# MINI_SYSTEM_RCT6.net
KiCad netlist of a schematic drawn in Altium Designer
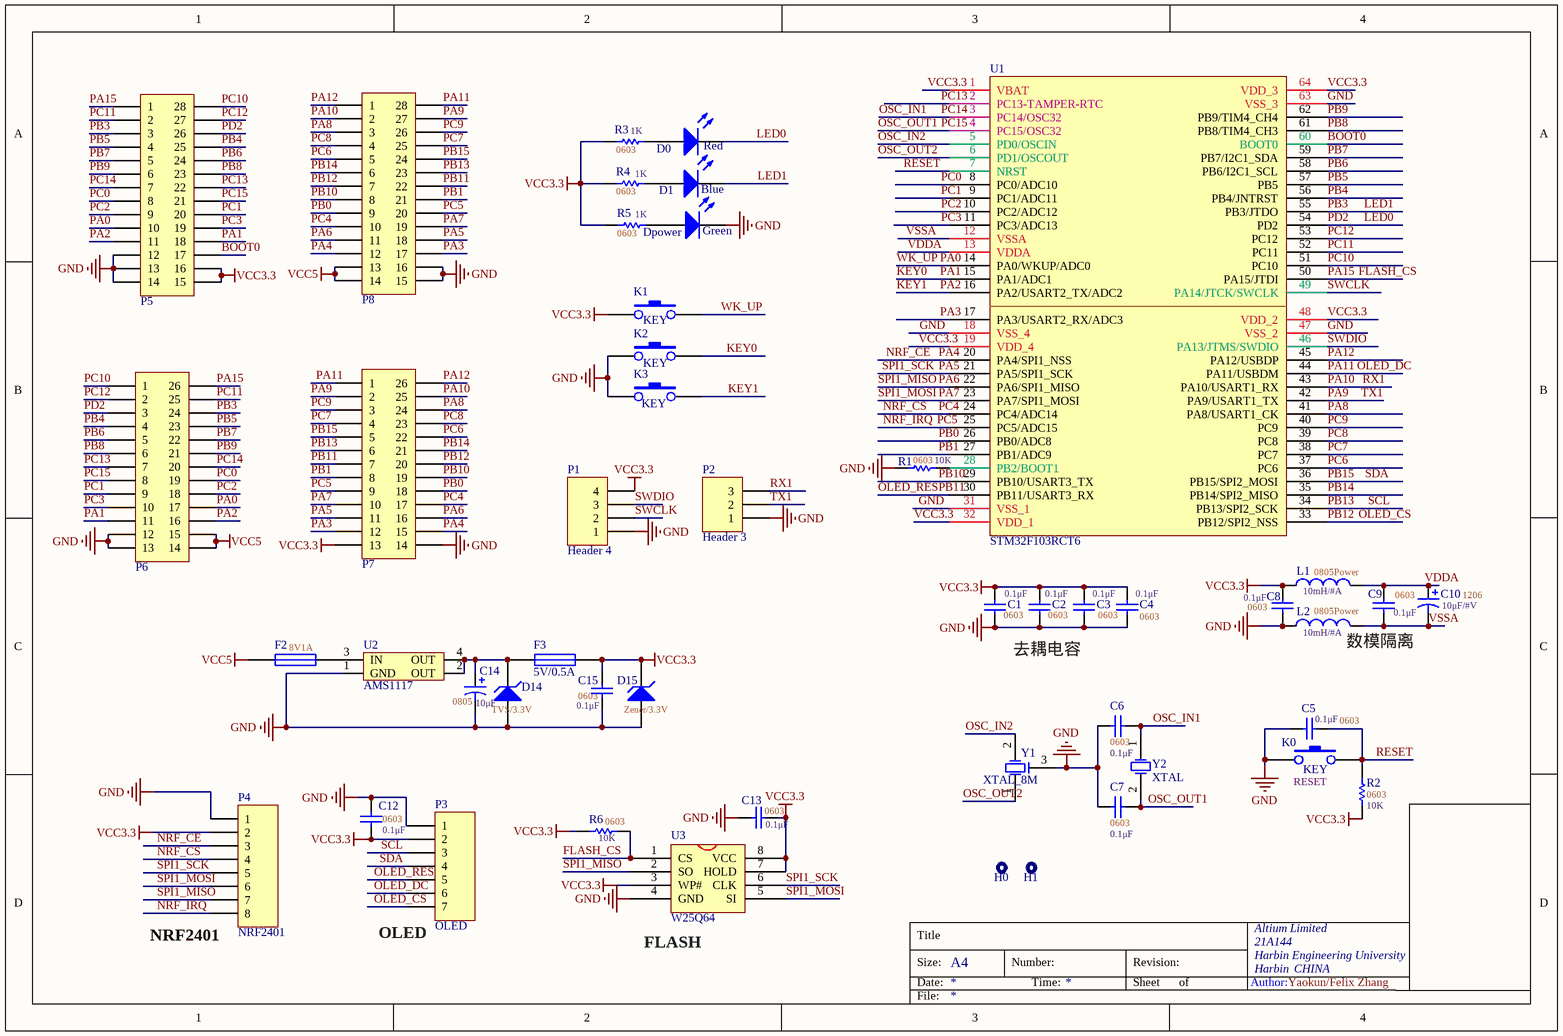
[diagram p0: MINI_SYSTEM_RCT6.SchDoc]

(export (version "E")
  (design (tool "Eeschema 10.0.6"))
  (components
    (comp (ref "C1")
      (value "0.1μF")
      (footprint "CAP_0603_16*08")
      (description "Capacitor")
      (fields
        (field (name "PACKAGEREFERENCE") "0603")
        (field (name "Comment") "0603")
        (field (name "PUBLISHER") "Altium Limited")
      )
      (libsource (lib "Belong_to_Kongkong") (part "Cap"))
    )
    (comp (ref "C2")
      (value "0.1μF")
      (footprint "CAP_0603_16*08")
      (description "Capacitor")
      (fields
        (field (name "PACKAGEREFERENCE") "0603")
        (field (name "Comment") "0603")
        (field (name "PUBLISHER") "Altium Limited")
      )
      (libsource (lib "Belong_to_Kongkong") (part "Cap"))
    )
    (comp (ref "C3")
      (value "0.1μF")
      (footprint "CAP_0603_16*08")
      (description "Capacitor")
      (fields
        (field (name "PACKAGEREFERENCE") "0603")
        (field (name "Comment") "0603")
        (field (name "PUBLISHER") "Altium Limited")
      )
      (libsource (lib "Belong_to_Kongkong") (part "Cap"))
    )
    (comp (ref "C4")
      (value "0.1μF")
      (footprint "CAP_0603_16*08")
      (description "Capacitor")
      (fields
        (field (name "PACKAGEREFERENCE") "0603")
        (field (name "Comment") "0603")
        (field (name "PUBLISHER") "Altium Limited")
      )
      (libsource (lib "Belong_to_Kongkong") (part "Cap"))
    )
    (comp (ref "C5")
      (value "0.1μF")
      (footprint "CAP_0603_16*08")
      (description "Capacitor")
      (fields
        (field (name "PACKAGEREFERENCE") "0603")
        (field (name "Comment") "0603")
        (field (name "PUBLISHER") "Altium Limited")
      )
      (libsource (lib "Belong_to_Kongkong") (part "Cap"))
    )
    (comp (ref "C6")
      (value "0.1μF")
      (footprint "CAP_0603_16*08")
      (description "Capacitor")
      (fields
        (field (name "PACKAGEREFERENCE") "0603")
        (field (name "Comment") "0603")
        (field (name "PUBLISHER") "Altium Limited")
      )
      (libsource (lib "Belong_to_Kongkong") (part "Cap"))
    )
    (comp (ref "C7")
      (value "0.1μF")
      (footprint "CAP_0603_16*08")
      (description "Capacitor")
      (fields
        (field (name "PACKAGEREFERENCE") "0603")
        (field (name "Comment") "0603")
        (field (name "PUBLISHER") "Altium Limited")
      )
      (libsource (lib "Belong_to_Kongkong") (part "Cap"))
    )
    (comp (ref "C8")
      (value "0.1μF")
      (footprint "CAP_0603_16*08")
      (description "Capacitor")
      (fields
        (field (name "PACKAGEREFERENCE") "0603")
        (field (name "Comment") "0603")
        (field (name "PUBLISHER") "Altium Limited")
      )
      (libsource (lib "Belong_to_Kongkong") (part "Cap"))
    )
    (comp (ref "C9")
      (value "0.1μF")
      (footprint "CAP_0603_16*08")
      (description "Capacitor")
      (fields
        (field (name "PACKAGEREFERENCE") "0603")
        (field (name "Comment") "0603")
        (field (name "PUBLISHER") "Altium Limited")
      )
      (libsource (lib "Belong_to_Kongkong") (part "Cap"))
    )
    (comp (ref "C10")
      (value "10μF/#V")
      (footprint "CAP_0805_20*12")
      (description "Polarized Capacitor (Axial)")
      (fields
        (field (name "PACKAGEREFERENCE") "1206")
        (field (name "Comment") "Polar")
        (field (name "PUBLISHER") "Altium Limited")
      )
      (libsource (lib "Belong_to_Kongkong") (part "Cap Pol"))
    )
    (comp (ref "C12")
      (value "0.1μF")
      (footprint "CAP_0603_16*08")
      (description "Capacitor")
      (fields
        (field (name "PACKAGEREFERENCE") "0603")
        (field (name "Comment") "0603")
        (field (name "PUBLISHER") "Altium Limited")
      )
      (libsource (lib "Belong_to_Kongkong") (part "Cap"))
    )
    (comp (ref "C13")
      (value "0.1μF")
      (footprint "CAP_0603_16*08")
      (description "Capacitor")
      (fields
        (field (name "PACKAGEREFERENCE") "0603")
        (field (name "Comment") "0603")
        (field (name "PUBLISHER") "Altium Limited")
      )
      (libsource (lib "Belong_to_Kongkong") (part "Cap"))
    )
    (comp (ref "C14")
      (value "10μF")
      (footprint "CAP_0805_20*12")
      (description "Polarized Capacitor (Axial)")
      (fields
        (field (name "PACKAGEREFERENCE") "0805")
        (field (name "Comment") "Polar")
        (field (name "PUBLISHER") "Altium Limited")
      )
      (libsource (lib "Belong_to_Kongkong") (part "Cap Pol"))
    )
    (comp (ref "C15")
      (value "0.1μF")
      (footprint "CAP_0603_16*08")
      (description "Capacitor")
      (fields
        (field (name "PACKAGEREFERENCE") "0603")
        (field (name "Comment") "0603")
        (field (name "PUBLISHER") "Altium Limited")
      )
      (libsource (lib "Belong_to_Kongkong") (part "Cap"))
    )
    (comp (ref "D0")
      (value "Red")
      (footprint "LED_0805")
      (description "Typical RED, GREEN, YELLOW, AMBER GaAs LED")
      (fields (field (name "PUBLISHER") "Altium Limited"))
      (libsource (lib "Belong_to_Kongkong") (part "LED"))
    )
    (comp (ref "D1")
      (value "Blue")
      (footprint "LED_0805")
      (description "Typical RED, GREEN, YELLOW, AMBER GaAs LED")
      (fields (field (name "PUBLISHER") "Altium Limited"))
      (libsource (lib "Belong_to_Kongkong") (part "LED"))
    )
    (comp (ref "D14")
      (value "TVS/3.3V")
      (footprint "SOD523")
      (description "Zener Diode")
      (fields (field (name "PUBLISHER") "Altium Limited"))
      (libsource (lib "Belong_to_Kongkong") (part "D Zener"))
    )
    (comp (ref "D15")
      (value "Zener/3.3V")
      (footprint "SOD323")
      (description "Zener Diode")
      (fields (field (name "PUBLISHER") "Altium Limited"))
      (libsource (lib "Belong_to_Kongkong") (part "D Zener"))
    )
    (comp (ref "Dpower")
      (value "Green")
      (footprint "LED_0805")
      (description "Typical RED, GREEN, YELLOW, AMBER GaAs LED")
      (fields (field (name "PUBLISHER") "Altium Limited"))
      (libsource (lib "Belong_to_Kongkong") (part "LED"))
    )
    (comp (ref "F2")
      (value "8V1A")
      (footprint "RES_0805_20*12")
      (description "Fuse")
      (fields (field (name "PUBLISHER") "Altium Limited"))
      (libsource (lib "Belong_to_Kongkong") (part "Fuse 1"))
    )
    (comp (ref "F3")
      (value "5V/0.5A")
      (footprint "RES_0805_20*12")
      (description "Fuse")
      (fields (field (name "PUBLISHER") "Altium Limited"))
      (libsource (lib "Belong_to_Kongkong") (part "Fuse 1"))
    )
    (comp (ref "H0")
      (value "Pad3mm")
      (footprint "PAD")
      (libsource (lib "Belong_to_Kongkong") (part "Pad3mm"))
    )
    (comp (ref "H1")
      (value "Pad3mm")
      (footprint "PAD")
      (libsource (lib "Belong_to_Kongkong") (part "Pad3mm"))
    )
    (comp (ref "K0")
      (value "KEY")
      (footprint "KEY_4")
      (fields (field (name "ALTIUM_UNNAMED_1") "RESET"))
      (libsource (lib "Belong_to_Kongkong") (part "KEY"))
    )
    (comp (ref "K1") (value "KEY") (footprint "KEY_2") (libsource (lib "Belong_to_Kongkong") (part "KEY")))
    (comp (ref "K2") (value "KEY") (footprint "KEY_2") (libsource (lib "Belong_to_Kongkong") (part "KEY")))
    (comp (ref "K3") (value "KEY") (footprint "KEY_2") (libsource (lib "Belong_to_Kongkong") (part "KEY")))
    (comp (ref "L1")
      (value "10mH/#A")
      (footprint "IND_0805_20*12")
      (description "Inductor")
      (fields
        (field (name "PACKAGEREFERENCE") "0805")
        (field (name "PACKAGEDESCRIPTION") "Power")
        (field (name "Comment") "MODEL?")
        (field (name "PUBLISHER") "Altium Limited")
      )
      (libsource (lib "Belong_to_Kongkong") (part "Inductor"))
    )
    (comp (ref "L2")
      (value "10mH/#A")
      (footprint "IND_0805_20*12")
      (description "Inductor")
      (fields
        (field (name "PACKAGEREFERENCE") "0805")
        (field (name "PACKAGEDESCRIPTION") "Power")
        (field (name "Comment") "MODEL?")
        (field (name "PUBLISHER") "Altium Limited")
      )
      (libsource (lib "Belong_to_Kongkong") (part "Inductor"))
    )
    (comp (ref "P1")
      (value "Header 4")
      (footprint "P4_OUT")
      (description "Header, 4-Pin")
      (fields (field (name "PUBLISHER") "Altium Limited"))
      (libsource (lib "Belong_to_Kongkong") (part "Header 4"))
    )
    (comp (ref "P2")
      (value "Header 3")
      (footprint "P3_OUT")
      (description "Header, 3-Pin")
      (fields (field (name "PUBLISHER") "Altium Limited"))
      (libsource (lib "Belong_to_Kongkong") (part "Header 3"))
    )
    (comp (ref "P3")
      (value "OLED")
      (footprint "HEADER1*7_PIN")
      (description "Header, 7-Pin")
      (fields (field (name "PUBLISHER") "Altium Limited"))
      (libsource (lib "Belong_to_Kongkong") (part "Header 7"))
    )
    (comp (ref "P4")
      (value "NRF2401")
      (footprint "HDR2X4")
      (description "Header, 8-Pin")
      (fields (field (name "PUBLISHER") "Altium Limited"))
      (libsource (lib "Belong_to_Kongkong") (part "Header 8"))
    )
    (comp (ref "P5")
      (value "HEADER")
      (footprint "HEADER2*14")
      (libsource (lib "Belong_to_Kongkong") (part "Header14*2"))
    )
    (comp (ref "P6")
      (value "Header")
      (footprint "HEADER2*13_SMD")
      (libsource (lib "Belong_to_Kongkong") (part "Header13*2"))
    )
    (comp (ref "P7")
      (value "Header")
      (footprint "HEADER2*13_SMD")
      (libsource (lib "Belong_to_Kongkong") (part "Header13*2"))
    )
    (comp (ref "P8")
      (value "HEADER")
      (footprint "HEADER2*14")
      (libsource (lib "Belong_to_Kongkong") (part "Header14*2"))
    )
    (comp (ref "R1")
      (value "10K")
      (footprint "RES_0603_16*08")
      (description "Resistor")
      (fields
        (field (name "PACKAGEREFERENCE") "0603")
        (field (name "Comment") "SMD")
        (field (name "PUBLISHER") "Altium Limited")
      )
      (libsource (lib "Belong_to_Kongkong") (part "RES_SMD"))
    )
    (comp (ref "R2")
      (value "10K")
      (footprint "RES_0603_16*08")
      (description "Resistor")
      (fields
        (field (name "PACKAGEREFERENCE") "0603")
        (field (name "Comment") "SMD")
        (field (name "PUBLISHER") "Altium Limited")
      )
      (libsource (lib "Belong_to_Kongkong") (part "RES_SMD"))
    )
    (comp (ref "R3")
      (value "1K")
      (footprint "RES_0603_16*08")
      (description "Resistor")
      (fields
        (field (name "PACKAGEREFERENCE") "0603")
        (field (name "Comment") "SMD")
        (field (name "PUBLISHER") "Altium Limited")
      )
      (libsource (lib "Belong_to_Kongkong") (part "RES_SMD"))
    )
    (comp (ref "R4")
      (value "1K")
      (footprint "RES_0603_16*08")
      (description "Resistor")
      (fields
        (field (name "PACKAGEREFERENCE") "0603")
        (field (name "Comment") "SMD")
        (field (name "PUBLISHER") "Altium Limited")
      )
      (libsource (lib "Belong_to_Kongkong") (part "RES_SMD"))
    )
    (comp (ref "R5")
      (value "1K")
      (footprint "RES_0603_16*08")
      (description "Resistor")
      (fields
        (field (name "PACKAGEREFERENCE") "0603")
        (field (name "Comment") "SMD")
        (field (name "PUBLISHER") "Altium Limited")
      )
      (libsource (lib "Belong_to_Kongkong") (part "RES_SMD"))
    )
    (comp (ref "R6")
      (value "10K")
      (footprint "RES_0603_16*08")
      (description "Resistor")
      (fields
        (field (name "PACKAGEREFERENCE") "0603")
        (field (name "Comment") "SMD")
        (field (name "PUBLISHER") "Altium Limited")
      )
      (libsource (lib "Belong_to_Kongkong") (part "RES_SMD"))
    )
    (comp (ref "U1")
      (value "STM32F103RCT6")
      (footprint "LQFP64_N")
      (libsource (lib "Belong_to_Kongkong") (part "STM32F103RBT6"))
    )
    (comp (ref "U2")
      (value "AMS1117")
      (footprint "SOT223_M")
      (libsource (lib "Belong_to_Kongkong") (part "AMS1117"))
    )
    (comp (ref "U3")
      (value "W25Q64")
      (footprint "SOIC-8")
      (description "flash")
      (libsource (lib "Belong_to_Kongkong") (part "W25Q64"))
    )
    (comp (ref "Y1")
      (value "XTAL_8M")
      (footprint "8M-cstcy")
      (libsource (lib "Belong_to_Kongkong") (part "XTAL_8M"))
    )
    (comp (ref "Y2")
      (value "XTAL")
      (footprint "XTAL32")
      (description "Crystal Oscillator")
      (fields (field (name "PUBLISHER") "Altium Limited"))
      (libsource (lib "Belong_to_Kongkong") (part "XTAL"))
    )
  )
  (nets
    (net (code "1") (name "/BOOT0") (class "Default")
      (node (ref "P5") (pin "17") (pinfunction "17_17") (pintype "passive"))
      (node (ref "U1") (pin "60") (pinfunction "BOOT0_60") (pintype "passive"))
    )
    (net (code "2") (name "/FLASH_CS") (class "Default")
      (node (ref "P5") (pin "1") (pinfunction "1_1") (pintype "passive"))
      (node (ref "P6") (pin "26") (pinfunction "26_26") (pintype "passive"))
      (node (ref "R6") (pin "2") (pinfunction "2_2") (pintype "passive"))
      (node (ref "U1") (pin "50") (pinfunction "PA15/JTDI_50") (pintype "passive"))
      (node (ref "U3") (pin "1") (pinfunction "CS_1") (pintype "passive"))
    )
    (net (code "3") (name "/KEY0") (class "Default")
      (node (ref "K2") (pin "2") (pinfunction "2_2") (pintype "passive"))
      (node (ref "P5") (pin "18") (pinfunction "18_18") (pintype "passive"))
      (node (ref "P6") (pin "11") (pinfunction "11_11") (pintype "passive"))
      (node (ref "U1") (pin "15") (pinfunction "PA1/ADC1_15") (pintype "passive"))
    )
    (net (code "4") (name "/KEY1") (class "Default")
      (node (ref "K3") (pin "2") (pinfunction "2_2") (pintype "passive"))
      (node (ref "P5") (pin "11") (pinfunction "11_11") (pintype "passive"))
      (node (ref "P6") (pin "16") (pinfunction "16_16") (pintype "passive"))
      (node (ref "U1") (pin "16") (pinfunction "PA2/USART2_TX/ADC2_16") (pintype "passive"))
    )
    (net (code "5") (name "/LED0") (class "Default")
      (node (ref "D0") (pin "2") (pinfunction "K_2") (pintype "passive"))
      (node (ref "P5") (pin "26") (pinfunction "26_26") (pintype "passive"))
      (node (ref "P6") (pin "3") (pinfunction "3_3") (pintype "passive"))
      (node (ref "U1") (pin "54") (pinfunction "PD2_54") (pintype "passive"))
    )
    (net (code "6") (name "/LED1") (class "Default")
      (node (ref "D1") (pin "2") (pinfunction "K_2") (pintype "passive"))
      (node (ref "P5") (pin "3") (pinfunction "3_3") (pintype "passive"))
      (node (ref "P6") (pin "24") (pinfunction "24_24") (pintype "passive"))
      (node (ref "U1") (pin "55") (pinfunction "PB3/JTDO_55") (pintype "passive"))
    )
    (net (code "7") (name "/NRF_CE") (class "Default")
      (node (ref "P4") (pin "3") (pinfunction "3_3") (pintype "passive"))
      (node (ref "P7") (pin "15") (pinfunction "15_15") (pintype "passive"))
      (node (ref "P8") (pin "12") (pinfunction "12_12") (pintype "passive"))
      (node (ref "U1") (pin "20") (pinfunction "PA4/SPI1_NSS_20") (pintype "passive"))
    )
    (net (code "8") (name "/NRF_CS") (class "Default")
      (node (ref "P4") (pin "4") (pinfunction "4_4") (pintype "passive"))
      (node (ref "P7") (pin "17") (pinfunction "17_17") (pintype "passive"))
      (node (ref "P8") (pin "10") (pinfunction "10_10") (pintype "passive"))
      (node (ref "U1") (pin "24") (pinfunction "PC4/ADC14_24") (pintype "passive"))
    )
    (net (code "9") (name "/NRF_IRQ") (class "Default")
      (node (ref "P4") (pin "8") (pinfunction "8_8") (pintype "passive"))
      (node (ref "P7") (pin "9") (pinfunction "9_9") (pintype "passive"))
      (node (ref "P8") (pin "20") (pinfunction "20_20") (pintype "passive"))
      (node (ref "U1") (pin "25") (pinfunction "PC5/ADC15_25") (pintype "passive"))
    )
    (net (code "10") (name "/OLED_CS") (class "Default")
      (node (ref "P3") (pin "7") (pinfunction "7_7") (pintype "passive"))
      (node (ref "P7") (pin "20") (pinfunction "20_20") (pintype "passive"))
      (node (ref "P8") (pin "7") (pinfunction "7_7") (pintype "passive"))
      (node (ref "U1") (pin "33") (pinfunction "PB12/SPI2_NSS_33") (pintype "passive"))
    )
    (net (code "11") (name "/OLED_DC") (class "Default")
      (node (ref "P3") (pin "6") (pinfunction "6_6") (pintype "passive"))
      (node (ref "P7") (pin "1") (pinfunction "1_1") (pintype "passive"))
      (node (ref "P8") (pin "28") (pinfunction "28_28") (pintype "passive"))
      (node (ref "U1") (pin "44") (pinfunction "PA11/USBDM_44") (pintype "passive"))
    )
    (net (code "12") (name "/OLED_RES") (class "Default")
      (node (ref "P3") (pin "5") (pinfunction "5_5") (pintype "passive"))
      (node (ref "P7") (pin "7") (pinfunction "7_7") (pintype "passive"))
      (node (ref "P8") (pin "22") (pinfunction "22_22") (pintype "passive"))
      (node (ref "U1") (pin "30") (pinfunction "PB11/USART3_RX_30") (pintype "passive"))
    )
    (net (code "13") (name "/OSC_IN1") (class "Default")
      (node (ref "C6") (pin "1") (pinfunction "1_1") (pintype "passive"))
      (node (ref "P5") (pin "7") (pinfunction "7_7") (pintype "passive"))
      (node (ref "P6") (pin "20") (pinfunction "20_20") (pintype "passive"))
      (node (ref "U1") (pin "3") (pinfunction "PC14/OSC32_3") (pintype "passive"))
      (node (ref "Y2") (pin "1") (pinfunction "OSC1_1") (pintype "passive"))
    )
    (net (code "14") (name "/OSC_IN2") (class "Default")
      (node (ref "U1") (pin "5") (pinfunction "PD0/OSCIN_5") (pintype "passive"))
      (node (ref "Y1") (pin "2") (pinfunction "OSC2_2") (pintype "passive"))
    )
    (net (code "15") (name "/OSC_OUT1") (class "Default")
      (node (ref "C7") (pin "1") (pinfunction "1_1") (pintype "passive"))
      (node (ref "P5") (pin "21") (pinfunction "21_21") (pintype "passive"))
      (node (ref "P6") (pin "8") (pinfunction "8_8") (pintype "passive"))
      (node (ref "U1") (pin "4") (pinfunction "PC15/OSC32_4") (pintype "passive"))
      (node (ref "Y2") (pin "2") (pinfunction "OSC2_2") (pintype "passive"))
    )
    (net (code "16") (name "/OSC_OUT2") (class "Default")
      (node (ref "U1") (pin "6") (pinfunction "PD1/OSCOUT_6") (pintype "passive"))
      (node (ref "Y1") (pin "1") (pinfunction "OSC1_1") (pintype "passive"))
    )
    (net (code "17") (name "/PA0") (class "Default")
      (node (ref "K1") (pin "2") (pinfunction "2_2") (pintype "passive"))
      (node (ref "P5") (pin "10") (pinfunction "10_10") (pintype "passive"))
      (node (ref "P6") (pin "17") (pinfunction "17_17") (pintype "passive"))
      (node (ref "U1") (pin "14") (pinfunction "PA0/WKUP/ADC0_14") (pintype "passive"))
    )
    (net (code "18") (name "/PA3") (class "Default")
      (node (ref "P7") (pin "12") (pinfunction "12_12") (pintype "passive"))
      (node (ref "P8") (pin "17") (pinfunction "17_17") (pintype "passive"))
      (node (ref "U1") (pin "17") (pinfunction "PA3/USART2_RX/ADC3_17") (pintype "passive"))
    )
    (net (code "19") (name "/PA5") (class "Default")
      (node (ref "P4") (pin "5") (pinfunction "5_5") (pintype "passive"))
      (node (ref "P7") (pin "11") (pinfunction "11_11") (pintype "passive"))
      (node (ref "P8") (pin "18") (pinfunction "18_18") (pintype "passive"))
      (node (ref "U1") (pin "21") (pinfunction "PA5/SPI1_SCK_21") (pintype "passive"))
      (node (ref "U3") (pin "6") (pinfunction "CLK_6") (pintype "passive"))
    )
    (net (code "20") (name "/PA6") (class "Default")
      (node (ref "P4") (pin "7") (pinfunction "7_7") (pintype "passive"))
      (node (ref "P7") (pin "16") (pinfunction "16_16") (pintype "passive"))
      (node (ref "P8") (pin "11") (pinfunction "11_11") (pintype "passive"))
      (node (ref "U1") (pin "22") (pinfunction "PA6/SPI1_MISO_22") (pintype "passive"))
      (node (ref "U3") (pin "2") (pinfunction "SO_2") (pintype "passive"))
    )
    (net (code "21") (name "/PA7") (class "Default")
      (node (ref "P4") (pin "6") (pinfunction "6_6") (pintype "passive"))
      (node (ref "P7") (pin "10") (pinfunction "10_10") (pintype "passive"))
      (node (ref "P8") (pin "19") (pinfunction "19_19") (pintype "passive"))
      (node (ref "U1") (pin "23") (pinfunction "PA7/SPI1_MOSI_23") (pintype "passive"))
      (node (ref "U3") (pin "5") (pinfunction "SI_5") (pintype "passive"))
    )
    (net (code "22") (name "/PA8") (class "Default")
      (node (ref "P7") (pin "24") (pinfunction "24_24") (pintype "passive"))
      (node (ref "P8") (pin "3") (pinfunction "3_3") (pintype "passive"))
      (node (ref "U1") (pin "41") (pinfunction "PA8/USART1_CK_41") (pintype "passive"))
    )
    (net (code "23") (name "/PA9") (class "Default")
      (node (ref "P2") (pin "2") (pinfunction "2_2") (pintype "passive"))
      (node (ref "P7") (pin "2") (pinfunction "2_2") (pintype "passive"))
      (node (ref "P8") (pin "27") (pinfunction "27_27") (pintype "passive"))
      (node (ref "U1") (pin "42") (pinfunction "PA9/USART1_TX_42") (pintype "passive"))
    )
    (net (code "24") (name "/PA10") (class "Default")
      (node (ref "P2") (pin "3") (pinfunction "3_3") (pintype "passive"))
      (node (ref "P7") (pin "25") (pinfunction "25_25") (pintype "passive"))
      (node (ref "P8") (pin "2") (pinfunction "2_2") (pintype "passive"))
      (node (ref "U1") (pin "43") (pinfunction "PA10/USART1_RX_43") (pintype "passive"))
    )
    (net (code "25") (name "/PA12") (class "Default")
      (node (ref "P7") (pin "26") (pinfunction "26_26") (pintype "passive"))
      (node (ref "P8") (pin "1") (pinfunction "1_1") (pintype "passive"))
      (node (ref "U1") (pin "45") (pinfunction "PA12/USBDP_45") (pintype "passive"))
    )
    (net (code "26") (name "/PB0") (class "Default")
      (node (ref "P7") (pin "18") (pinfunction "18_18") (pintype "passive"))
      (node (ref "P8") (pin "9") (pinfunction "9_9") (pintype "passive"))
      (node (ref "U1") (pin "26") (pinfunction "PB0/ADC8_26") (pintype "passive"))
    )
    (net (code "27") (name "/PB1") (class "Default")
      (node (ref "P7") (pin "8") (pinfunction "8_8") (pintype "passive"))
      (node (ref "P8") (pin "21") (pinfunction "21_21") (pintype "passive"))
      (node (ref "U1") (pin "27") (pinfunction "PB1/ADC9_27") (pintype "passive"))
    )
    (net (code "28") (name "/PB4") (class "Default")
      (node (ref "P5") (pin "25") (pinfunction "25_25") (pintype "passive"))
      (node (ref "P6") (pin "4") (pinfunction "4_4") (pintype "passive"))
      (node (ref "U1") (pin "56") (pinfunction "PB4/JNTRST_56") (pintype "passive"))
    )
    (net (code "29") (name "/PB5") (class "Default")
      (node (ref "P5") (pin "4") (pinfunction "4_4") (pintype "passive"))
      (node (ref "P6") (pin "23") (pinfunction "23_23") (pintype "passive"))
      (node (ref "U1") (pin "57") (pinfunction "PB5_57") (pintype "passive"))
    )
    (net (code "30") (name "/PB6") (class "Default")
      (node (ref "P5") (pin "24") (pinfunction "24_24") (pintype "passive"))
      (node (ref "P6") (pin "5") (pinfunction "5_5") (pintype "passive"))
      (node (ref "U1") (pin "58") (pinfunction "PB6/I2C1_SCL_58") (pintype "passive"))
    )
    (net (code "31") (name "/PB7") (class "Default")
      (node (ref "P5") (pin "5") (pinfunction "5_5") (pintype "passive"))
      (node (ref "P6") (pin "22") (pinfunction "22_22") (pintype "passive"))
      (node (ref "U1") (pin "59") (pinfunction "PB7/I2C1_SDA_59") (pintype "passive"))
    )
    (net (code "32") (name "/PB8") (class "Default")
      (node (ref "P5") (pin "23") (pinfunction "23_23") (pintype "passive"))
      (node (ref "P6") (pin "6") (pinfunction "6_6") (pintype "passive"))
      (node (ref "U1") (pin "61") (pinfunction "PB8/TIM4_CH3_61") (pintype "passive"))
    )
    (net (code "33") (name "/PB9") (class "Default")
      (node (ref "P5") (pin "6") (pinfunction "6_6") (pintype "passive"))
      (node (ref "P6") (pin "21") (pinfunction "21_21") (pintype "passive"))
      (node (ref "U1") (pin "62") (pinfunction "PB9/TIM4_CH4_62") (pintype "passive"))
    )
    (net (code "34") (name "/PB10") (class "Default")
      (node (ref "P7") (pin "19") (pinfunction "19_19") (pintype "passive"))
      (node (ref "P8") (pin "8") (pinfunction "8_8") (pintype "passive"))
      (node (ref "U1") (pin "29") (pinfunction "PB10/USART3_TX_29") (pintype "passive"))
    )
    (net (code "35") (name "/PB13") (class "Default")
      (node (ref "P3") (pin "3") (pinfunction "3_3") (pintype "passive"))
      (node (ref "P7") (pin "6") (pinfunction "6_6") (pintype "passive"))
      (node (ref "P8") (pin "23") (pinfunction "23_23") (pintype "passive"))
      (node (ref "U1") (pin "34") (pinfunction "PB13/SPI2_SCK_34") (pintype "passive"))
    )
    (net (code "36") (name "/PB14") (class "Default")
      (node (ref "P7") (pin "21") (pinfunction "21_21") (pintype "passive"))
      (node (ref "P8") (pin "6") (pinfunction "6_6") (pintype "passive"))
      (node (ref "U1") (pin "35") (pinfunction "PB14/SPI2_MISO_35") (pintype "passive"))
    )
    (net (code "37") (name "/PB15") (class "Default")
      (node (ref "P3") (pin "4") (pinfunction "4_4") (pintype "passive"))
      (node (ref "P7") (pin "5") (pinfunction "5_5") (pintype "passive"))
      (node (ref "P8") (pin "24") (pinfunction "24_24") (pintype "passive"))
      (node (ref "U1") (pin "36") (pinfunction "PB15/SPI2_MOSI_36") (pintype "passive"))
    )
    (net (code "38") (name "/PC0") (class "Default")
      (node (ref "P5") (pin "8") (pinfunction "8_8") (pintype "passive"))
      (node (ref "P6") (pin "19") (pinfunction "19_19") (pintype "passive"))
      (node (ref "U1") (pin "8") (pinfunction "PC0/ADC10_8") (pintype "passive"))
    )
    (net (code "39") (name "/PC1") (class "Default")
      (node (ref "P5") (pin "20") (pinfunction "20_20") (pintype "passive"))
      (node (ref "P6") (pin "9") (pinfunction "9_9") (pintype "passive"))
      (node (ref "U1") (pin "9") (pinfunction "PC1/ADC11_9") (pintype "passive"))
    )
    (net (code "40") (name "/PC2") (class "Default")
      (node (ref "P5") (pin "9") (pinfunction "9_9") (pintype "passive"))
      (node (ref "P6") (pin "18") (pinfunction "18_18") (pintype "passive"))
      (node (ref "U1") (pin "10") (pinfunction "PC2/ADC12_10") (pintype "passive"))
    )
    (net (code "41") (name "/PC3") (class "Default")
      (node (ref "P5") (pin "19") (pinfunction "19_19") (pintype "passive"))
      (node (ref "P6") (pin "10") (pinfunction "10_10") (pintype "passive"))
      (node (ref "U1") (pin "11") (pinfunction "PC3/ADC13_11") (pintype "passive"))
    )
    (net (code "42") (name "/PC6") (class "Default")
      (node (ref "P7") (pin "22") (pinfunction "22_22") (pintype "passive"))
      (node (ref "P8") (pin "5") (pinfunction "5_5") (pintype "passive"))
      (node (ref "U1") (pin "37") (pinfunction "PC6_37") (pintype "passive"))
    )
    (net (code "43") (name "/PC7") (class "Default")
      (node (ref "P7") (pin "4") (pinfunction "4_4") (pintype "passive"))
      (node (ref "P8") (pin "25") (pinfunction "25_25") (pintype "passive"))
      (node (ref "U1") (pin "38") (pinfunction "PC7_38") (pintype "passive"))
    )
    (net (code "44") (name "/PC8") (class "Default")
      (node (ref "P7") (pin "23") (pinfunction "23_23") (pintype "passive"))
      (node (ref "P8") (pin "4") (pinfunction "4_4") (pintype "passive"))
      (node (ref "U1") (pin "39") (pinfunction "PC8_39") (pintype "passive"))
    )
    (net (code "45") (name "/PC9") (class "Default")
      (node (ref "P7") (pin "3") (pinfunction "3_3") (pintype "passive"))
      (node (ref "P8") (pin "26") (pinfunction "26_26") (pintype "passive"))
      (node (ref "U1") (pin "40") (pinfunction "PC9_40") (pintype "passive"))
    )
    (net (code "46") (name "/PC10") (class "Default")
      (node (ref "P5") (pin "28") (pinfunction "28_28") (pintype "passive"))
      (node (ref "P6") (pin "1") (pinfunction "1_1") (pintype "passive"))
      (node (ref "U1") (pin "51") (pinfunction "PC10_51") (pintype "passive"))
    )
    (net (code "47") (name "/PC11") (class "Default")
      (node (ref "P5") (pin "2") (pinfunction "2_2") (pintype "passive"))
      (node (ref "P6") (pin "25") (pinfunction "25_25") (pintype "passive"))
      (node (ref "U1") (pin "52") (pinfunction "PC11_52") (pintype "passive"))
    )
    (net (code "48") (name "/PC12") (class "Default")
      (node (ref "P5") (pin "27") (pinfunction "27_27") (pintype "passive"))
      (node (ref "P6") (pin "2") (pinfunction "2_2") (pintype "passive"))
      (node (ref "U1") (pin "53") (pinfunction "PC12_53") (pintype "passive"))
    )
    (net (code "49") (name "/PC13") (class "Default")
      (node (ref "P5") (pin "22") (pinfunction "22_22") (pintype "passive"))
      (node (ref "P6") (pin "7") (pinfunction "7_7") (pintype "passive"))
      (node (ref "U1") (pin "2") (pinfunction "PC13-TAMPER-RTC_2") (pintype "passive"))
    )
    (net (code "50") (name "/RESET") (class "Default")
      (node (ref "C5") (pin "2") (pinfunction "2_2") (pintype "passive"))
      (node (ref "K0") (pin "2") (pinfunction "2_2") (pintype "passive"))
      (node (ref "R2") (pin "2") (pinfunction "2_2") (pintype "passive"))
      (node (ref "U1") (pin "7") (pinfunction "NRST_7") (pintype "passive"))
    )
    (net (code "51") (name "/SWCLK") (class "Default")
      (node (ref "P1") (pin "2") (pinfunction "2_2") (pintype "passive"))
      (node (ref "U1") (pin "49") (pinfunction "PA14/JTCK/SWCLK_49") (pintype "passive"))
    )
    (net (code "52") (name "/SWDIO") (class "Default")
      (node (ref "P1") (pin "3") (pinfunction "3_3") (pintype "passive"))
      (node (ref "U1") (pin "46") (pinfunction "PA13/JTMS/SWDIO_46") (pintype "passive"))
    )
    (net (code "53") (name "/VDDA") (class "Default")
      (node (ref "C10") (pin "1") (pinfunction "1_1") (pintype "passive"))
      (node (ref "C9") (pin "2") (pinfunction "2_2") (pintype "passive"))
      (node (ref "L1") (pin "2") (pinfunction "2_2") (pintype "passive"))
      (node (ref "U1") (pin "13") (pinfunction "VDDA_13") (pintype "passive"))
    )
    (net (code "54") (name "/VSSA") (class "Default")
      (node (ref "C10") (pin "2") (pinfunction "2_2") (pintype "passive"))
      (node (ref "C9") (pin "1") (pinfunction "1_1") (pintype "passive"))
      (node (ref "L2") (pin "2") (pinfunction "2_2") (pintype "passive"))
      (node (ref "U1") (pin "12") (pinfunction "VSSA_12") (pintype "passive"))
    )
    (net (code "55") (name "GND") (class "Default")
      (node (ref "C1") (pin "2") (pinfunction "2_2") (pintype "passive"))
      (node (ref "C12") (pin "2") (pinfunction "2_2") (pintype "passive"))
      (node (ref "C13") (pin "1") (pinfunction "1_1") (pintype "passive"))
      (node (ref "C14") (pin "2") (pinfunction "2_2") (pintype "passive"))
      (node (ref "C15") (pin "1") (pinfunction "1_1") (pintype "passive"))
      (node (ref "C2") (pin "2") (pinfunction "2_2") (pintype "passive"))
      (node (ref "C3") (pin "2") (pinfunction "2_2") (pintype "passive"))
      (node (ref "C4") (pin "1") (pinfunction "1_1") (pintype "passive"))
      (node (ref "C5") (pin "1") (pinfunction "1_1") (pintype "passive"))
      (node (ref "C6") (pin "2") (pinfunction "2_2") (pintype "passive"))
      (node (ref "C7") (pin "2") (pinfunction "2_2") (pintype "passive"))
      (node (ref "C8") (pin "1") (pinfunction "1_1") (pintype "passive"))
      (node (ref "D14") (pin "1") (pinfunction "A_1") (pintype "passive"))
      (node (ref "D15") (pin "1") (pinfunction "A_1") (pintype "passive"))
      (node (ref "Dpower") (pin "2") (pinfunction "K_2") (pintype "passive"))
      (node (ref "K0") (pin "1") (pinfunction "1_1") (pintype "passive"))
      (node (ref "K2") (pin "1") (pinfunction "1_1") (pintype "passive"))
      (node (ref "K3") (pin "1") (pinfunction "1_1") (pintype "passive"))
      (node (ref "L2") (pin "1") (pinfunction "1_1") (pintype "passive"))
      (node (ref "P1") (pin "1") (pinfunction "1_1") (pintype "passive"))
      (node (ref "P2") (pin "1") (pinfunction "1_1") (pintype "passive"))
      (node (ref "P3") (pin "1") (pinfunction "1_1") (pintype "passive"))
      (node (ref "P4") (pin "1") (pinfunction "1_1") (pintype "passive"))
      (node (ref "P5") (pin "12") (pinfunction "12_12") (pintype "passive"))
      (node (ref "P5") (pin "13") (pinfunction "13_13") (pintype "passive"))
      (node (ref "P5") (pin "14") (pinfunction "14_14") (pintype "passive"))
      (node (ref "P6") (pin "12") (pinfunction "12_12") (pintype "passive"))
      (node (ref "P6") (pin "13") (pinfunction "13_13") (pintype "passive"))
      (node (ref "P7") (pin "14") (pinfunction "14_14") (pintype "passive"))
      (node (ref "P8") (pin "15") (pinfunction "15_15") (pintype "passive"))
      (node (ref "P8") (pin "16") (pinfunction "16_16") (pintype "passive"))
      (node (ref "R1") (pin "1") (pinfunction "1_1") (pintype "passive"))
      (node (ref "U1") (pin "18") (pinfunction "VSS_4_18") (pintype "passive"))
      (node (ref "U1") (pin "31") (pinfunction "VSS_1_31") (pintype "passive"))
      (node (ref "U1") (pin "47") (pinfunction "VSS_2_47") (pintype "passive"))
      (node (ref "U1") (pin "63") (pinfunction "VSS_3_63") (pintype "passive"))
      (node (ref "U2") (pin "1") (pinfunction "GND_1") (pintype "passive"))
      (node (ref "U3") (pin "4") (pinfunction "GND_4") (pintype "passive"))
      (node (ref "Y1") (pin "3") (pinfunction "OSC3_3") (pintype "passive"))
    )
    (net (code "56") (name "Net-(D0-A)") (class "Default")
      (node (ref "D0") (pin "1") (pinfunction "A_1") (pintype "passive"))
      (node (ref "R3") (pin "2") (pinfunction "2_2") (pintype "passive"))
    )
    (net (code "57") (name "Net-(D1-A)") (class "Default")
      (node (ref "D1") (pin "1") (pinfunction "A_1") (pintype "passive"))
      (node (ref "R4") (pin "2") (pinfunction "2_2") (pintype "passive"))
    )
    (net (code "58") (name "Net-(D14-K)") (class "Default")
      (node (ref "C14") (pin "1") (pinfunction "1_1") (pintype "passive"))
      (node (ref "D14") (pin "2") (pinfunction "K_2") (pintype "passive"))
      (node (ref "F3") (pin "1") (pinfunction "1_1") (pintype "passive"))
      (node (ref "U2") (pin "2") (pinfunction "OUT_2") (pintype "passive"))
      (node (ref "U2") (pin "4") (pinfunction "OUT_4") (pintype "passive"))
    )
    (net (code "59") (name "Net-(Dpower-A)") (class "Default")
      (node (ref "Dpower") (pin "1") (pinfunction "A_1") (pintype "passive"))
      (node (ref "R5") (pin "2") (pinfunction "2_2") (pintype "passive"))
    )
    (net (code "60") (name "Net-(U1-PB2{slash}BOOT1)") (class "Default")
      (node (ref "R1") (pin "2") (pinfunction "2_2") (pintype "passive"))
      (node (ref "U1") (pin "28") (pinfunction "PB2/BOOT1_28") (pintype "passive"))
    )
    (net (code "61") (name "Net-(U2-IN)") (class "Default")
      (node (ref "F2") (pin "2") (pinfunction "2_2") (pintype "passive"))
      (node (ref "U2") (pin "3") (pinfunction "IN_3") (pintype "passive"))
    )
    (net (code "62") (name "VCC3.3") (class "Default")
      (node (ref "C1") (pin "1") (pinfunction "1_1") (pintype "passive"))
      (node (ref "C12") (pin "1") (pinfunction "1_1") (pintype "passive"))
      (node (ref "C13") (pin "2") (pinfunction "2_2") (pintype "passive"))
      (node (ref "C15") (pin "2") (pinfunction "2_2") (pintype "passive"))
      (node (ref "C2") (pin "1") (pinfunction "1_1") (pintype "passive"))
      (node (ref "C3") (pin "1") (pinfunction "1_1") (pintype "passive"))
      (node (ref "C4") (pin "2") (pinfunction "2_2") (pintype "passive"))
      (node (ref "C8") (pin "2") (pinfunction "2_2") (pintype "passive"))
      (node (ref "D15") (pin "2") (pinfunction "K_2") (pintype "passive"))
      (node (ref "F3") (pin "2") (pinfunction "2_2") (pintype "passive"))
      (node (ref "K1") (pin "1") (pinfunction "1_1") (pintype "passive"))
      (node (ref "L1") (pin "1") (pinfunction "1_1") (pintype "passive"))
      (node (ref "P1") (pin "4") (pinfunction "4_4") (pintype "passive"))
      (node (ref "P3") (pin "2") (pinfunction "2_2") (pintype "passive"))
      (node (ref "P4") (pin "2") (pinfunction "2_2") (pintype "passive"))
      (node (ref "P5") (pin "15") (pinfunction "15_15") (pintype "passive"))
      (node (ref "P5") (pin "16") (pinfunction "16_16") (pintype "passive"))
      (node (ref "P7") (pin "13") (pinfunction "13_13") (pintype "passive"))
      (node (ref "R2") (pin "1") (pinfunction "1_1") (pintype "passive"))
      (node (ref "R3") (pin "1") (pinfunction "1_1") (pintype "passive"))
      (node (ref "R4") (pin "1") (pinfunction "1_1") (pintype "passive"))
      (node (ref "R5") (pin "1") (pinfunction "1_1") (pintype "passive"))
      (node (ref "R6") (pin "1") (pinfunction "1_1") (pintype "passive"))
      (node (ref "U1") (pin "1") (pinfunction "VBAT_1") (pintype "passive"))
      (node (ref "U1") (pin "19") (pinfunction "VDD_4_19") (pintype "passive"))
      (node (ref "U1") (pin "32") (pinfunction "VDD_1_32") (pintype "passive"))
      (node (ref "U1") (pin "48") (pinfunction "VDD_2_48") (pintype "passive"))
      (node (ref "U1") (pin "64") (pinfunction "VDD_3_64") (pintype "passive"))
      (node (ref "U3") (pin "3") (pinfunction "WP#_3") (pintype "passive"))
      (node (ref "U3") (pin "7") (pinfunction "HOLD_7") (pintype "passive"))
      (node (ref "U3") (pin "8") (pinfunction "VCC_8") (pintype "passive"))
    )
    (net (code "63") (name "VCC5") (class "Default")
      (node (ref "F2") (pin "1") (pinfunction "1_1") (pintype "passive"))
      (node (ref "P6") (pin "14") (pinfunction "14_14") (pintype "passive"))
      (node (ref "P6") (pin "15") (pinfunction "15_15") (pintype "passive"))
      (node (ref "P8") (pin "13") (pinfunction "13_13") (pintype "passive"))
      (node (ref "P8") (pin "14") (pinfunction "14_14") (pintype "passive"))
    )
  )
)
